# PhychipDevelopmentBoard.net
KiCad netlist of a schematic drawn in EAGLE
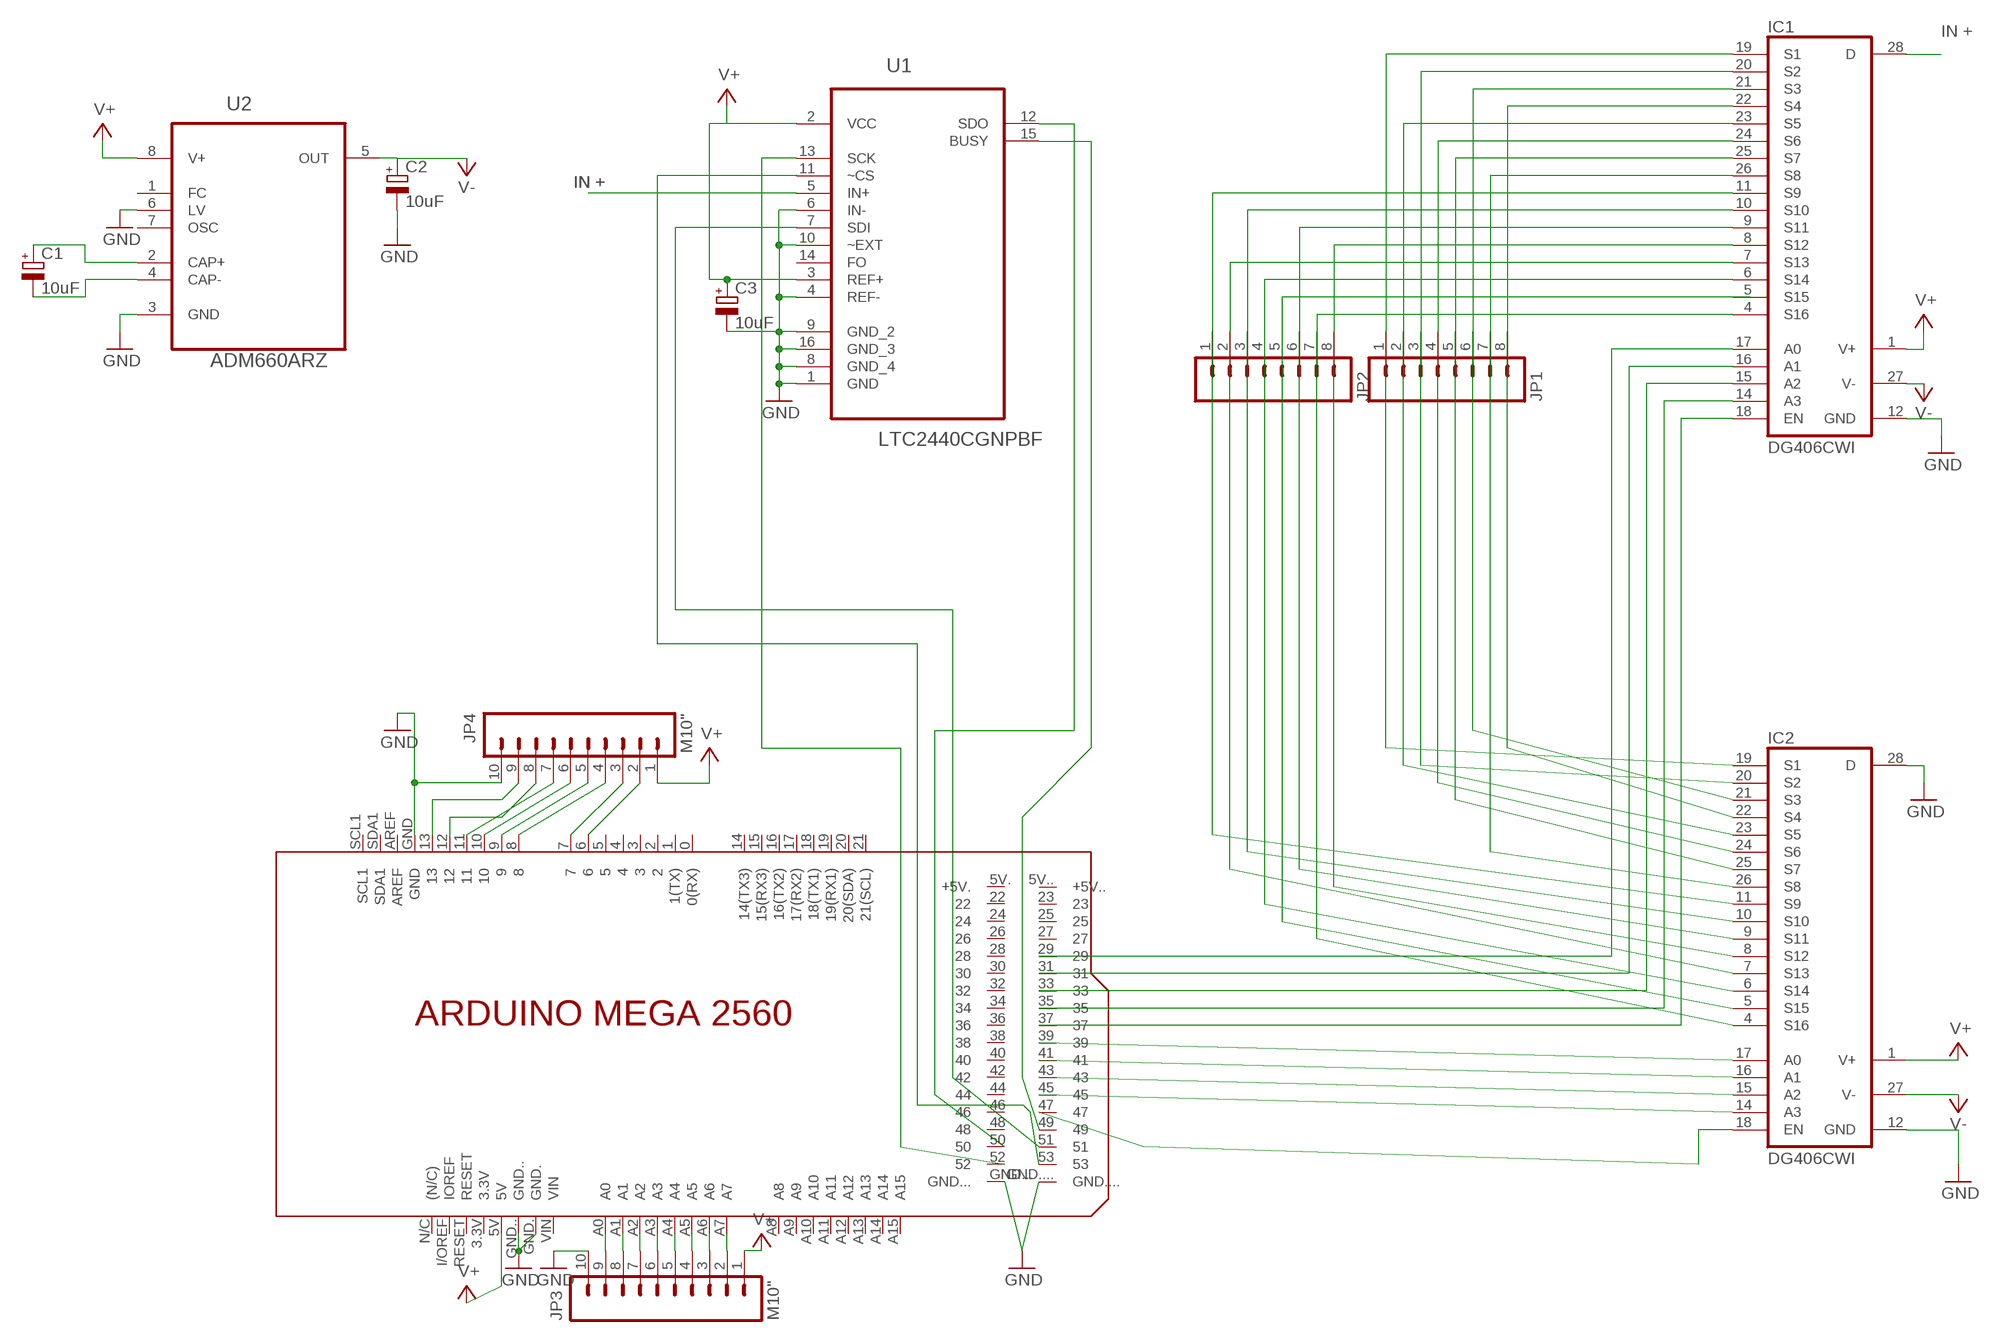
[diagram p0: schematic, sheet 1]

(export (version "E")
  (design (tool "Eeschema 10.0.6"))
  (components
    (comp (ref "C1")
      (value "10uF")
      (footprint "eagle-import:153CLV-0505")
      (libsource (lib "eagle-import") (part "CPOL-EU153CLV-0505"))
    )
    (comp (ref "C2")
      (value "10uF")
      (footprint "eagle-import:153CLV-0505")
      (libsource (lib "eagle-import") (part "CPOL-EU153CLV-0505"))
    )
    (comp (ref "C3")
      (value "10uF")
      (footprint "eagle-import:153CLV-0505")
      (libsource (lib "eagle-import") (part "CPOL-EU153CLV-0505"))
    )
    (comp (ref "IC1")
      (value "DG406CWI")
      (footprint "eagle-import:SO28L")
      (fields (field (name "MF") "MAXIM"))
      (libsource (lib "eagle-import") (part "DG406CWI"))
    )
    (comp (ref "IC2")
      (value "DG406CWI")
      (footprint "eagle-import:SO28L")
      (fields (field (name "MF") "MAXIM"))
      (libsource (lib "eagle-import") (part "DG406CWI"))
    )
    (comp (ref "JP1")
      (value "M08")
      (footprint "eagle-import:1X08")
      (libsource (lib "eagle-import") (part "M08"))
    )
    (comp (ref "JP2")
      (value "M08")
      (footprint "eagle-import:1X08")
      (libsource (lib "eagle-import") (part "M08"))
    )
    (comp (ref "JP3")
      (value "M10\"")
      (footprint "eagle-import:1X10")
      (libsource (lib "eagle-import") (part "M10{dblquote}"))
    )
    (comp (ref "JP4")
      (value "M10\"")
      (footprint "eagle-import:1X10")
      (libsource (lib "eagle-import") (part "M10{dblquote}"))
    )
    (comp (ref "PCB1")
      (value "ARDUINO_MEGA2560")
      (footprint "eagle-import:ARDUINO_MEGA2560")
      (libsource (lib "eagle-import") (part "ARDUINO_MEGA2560"))
    )
    (comp (ref "U1")
      (value "LTC2440CGNPBF")
      (footprint "eagle-import:SOP63P600X175-16N")
      (fields (field (name "MPN") "LTC2440CGN#PBF"))
      (libsource (lib "eagle-import") (part "LTC2440CGNPBF"))
    )
    (comp (ref "U2")
      (value "ADM660ARZ")
      (footprint "eagle-import:SOIC127P600X175-8N")
      (libsource (lib "eagle-import") (part "ADM660ARZ"))
    )
  )
  (nets
    (net (code "1") (name "/IN+") (class "Default")
      (node (ref "IC1") (pin "28") (pinfunction "D_28") (pintype "passive"))
      (node (ref "U1") (pin "5") (pinfunction "IN+_5") (pintype "input"))
    )
    (net (code "2") (name "GND") (class "Default")
      (node (ref "C2") (pin "-") (pinfunction "-_-") (pintype "passive"))
      (node (ref "C3") (pin "-") (pinfunction "-_-") (pintype "passive"))
      (node (ref "IC1") (pin "12") (pinfunction "GND_12") (pintype "power_in"))
      (node (ref "IC2") (pin "12") (pinfunction "GND_12") (pintype "power_in"))
      (node (ref "IC2") (pin "28") (pinfunction "D_28") (pintype "passive"))
      (node (ref "JP3") (pin "10") (pinfunction "10_10") (pintype "passive"))
      (node (ref "JP4") (pin "10") (pinfunction "10_10") (pintype "passive"))
      (node (ref "PCB1") (pin "GND") (pinfunction "GND_GND") (pintype "bidirectional"))
      (node (ref "PCB1") (pin "GND.") (pinfunction "GND._GND.") (pintype "bidirectional"))
      (node (ref "PCB1") (pin "GND..") (pinfunction "GND.._GND..") (pintype "bidirectional"))
      (node (ref "PCB1") (pin "GND...") (pinfunction "GND..._GND...") (pintype "bidirectional"))
      (node (ref "PCB1") (pin "GND....") (pinfunction "GND...._GND....") (pintype "bidirectional"))
      (node (ref "U1") (pin "1") (pinfunction "GND_1") (pintype "passive"))
      (node (ref "U1") (pin "10") (pinfunction "~{EXT}_10") (pintype "input"))
      (node (ref "U1") (pin "16") (pinfunction "GND_3_16") (pintype "passive"))
      (node (ref "U1") (pin "4") (pinfunction "REF-_4") (pintype "input"))
      (node (ref "U1") (pin "6") (pinfunction "IN-_6") (pintype "input"))
      (node (ref "U1") (pin "8") (pinfunction "GND_4_8") (pintype "passive"))
      (node (ref "U1") (pin "9") (pinfunction "GND_2_9") (pintype "passive"))
      (node (ref "U2") (pin "3") (pinfunction "GND_3") (pintype "passive"))
      (node (ref "U2") (pin "6") (pinfunction "LV_6") (pintype "input"))
    )
    (net (code "3") (name "Net-(IC1-A0)") (class "Default")
      (node (ref "IC1") (pin "17") (pinfunction "A0_17") (pintype "input"))
      (node (ref "PCB1") (pin "29") (pinfunction "29_29") (pintype "bidirectional"))
    )
    (net (code "4") (name "Net-(IC1-A1)") (class "Default")
      (node (ref "IC1") (pin "16") (pinfunction "A1_16") (pintype "input"))
      (node (ref "PCB1") (pin "31") (pinfunction "31_31") (pintype "bidirectional"))
    )
    (net (code "5") (name "Net-(IC1-A2)") (class "Default")
      (node (ref "IC1") (pin "15") (pinfunction "A2_15") (pintype "input"))
      (node (ref "PCB1") (pin "33") (pinfunction "33_33") (pintype "bidirectional"))
    )
    (net (code "6") (name "Net-(IC1-A3)") (class "Default")
      (node (ref "IC1") (pin "14") (pinfunction "A3_14") (pintype "input"))
      (node (ref "PCB1") (pin "35") (pinfunction "35_35") (pintype "bidirectional"))
    )
    (net (code "7") (name "Net-(IC1-EN)") (class "Default")
      (node (ref "IC1") (pin "18") (pinfunction "EN_18") (pintype "input"))
      (node (ref "PCB1") (pin "37") (pinfunction "37_37") (pintype "bidirectional"))
    )
    (net (code "8") (name "Net-(IC1-S1)") (class "Default")
      (node (ref "IC1") (pin "19") (pinfunction "S1_19") (pintype "passive"))
      (node (ref "IC2") (pin "19") (pinfunction "S1_19") (pintype "passive"))
      (node (ref "JP1") (pin "1") (pinfunction "1_1") (pintype "passive"))
    )
    (net (code "9") (name "Net-(IC1-S2)") (class "Default")
      (node (ref "IC1") (pin "20") (pinfunction "S2_20") (pintype "passive"))
      (node (ref "IC2") (pin "20") (pinfunction "S2_20") (pintype "passive"))
      (node (ref "JP1") (pin "3") (pinfunction "3_3") (pintype "passive"))
    )
    (net (code "10") (name "Net-(IC1-S3)") (class "Default")
      (node (ref "IC1") (pin "21") (pinfunction "S3_21") (pintype "passive"))
      (node (ref "IC2") (pin "21") (pinfunction "S3_21") (pintype "passive"))
      (node (ref "JP1") (pin "6") (pinfunction "6_6") (pintype "passive"))
    )
    (net (code "11") (name "Net-(IC1-S4)") (class "Default")
      (node (ref "IC1") (pin "22") (pinfunction "S4_22") (pintype "passive"))
      (node (ref "IC2") (pin "22") (pinfunction "S4_22") (pintype "passive"))
      (node (ref "JP1") (pin "8") (pinfunction "8_8") (pintype "passive"))
    )
    (net (code "12") (name "Net-(IC1-S5)") (class "Default")
      (node (ref "IC1") (pin "23") (pinfunction "S5_23") (pintype "passive"))
      (node (ref "IC2") (pin "23") (pinfunction "S5_23") (pintype "passive"))
      (node (ref "JP1") (pin "2") (pinfunction "2_2") (pintype "passive"))
    )
    (net (code "13") (name "Net-(IC1-S6)") (class "Default")
      (node (ref "IC1") (pin "24") (pinfunction "S6_24") (pintype "passive"))
      (node (ref "IC2") (pin "24") (pinfunction "S6_24") (pintype "passive"))
      (node (ref "JP1") (pin "4") (pinfunction "4_4") (pintype "passive"))
    )
    (net (code "14") (name "Net-(IC1-S7)") (class "Default")
      (node (ref "IC1") (pin "25") (pinfunction "S7_25") (pintype "passive"))
      (node (ref "IC2") (pin "25") (pinfunction "S7_25") (pintype "passive"))
      (node (ref "JP1") (pin "5") (pinfunction "5_5") (pintype "passive"))
    )
    (net (code "15") (name "Net-(IC1-S8)") (class "Default")
      (node (ref "IC1") (pin "26") (pinfunction "S8_26") (pintype "passive"))
      (node (ref "IC2") (pin "26") (pinfunction "S8_26") (pintype "passive"))
      (node (ref "JP1") (pin "7") (pinfunction "7_7") (pintype "passive"))
    )
    (net (code "16") (name "Net-(IC1-S9)") (class "Default")
      (node (ref "IC1") (pin "11") (pinfunction "S9_11") (pintype "passive"))
      (node (ref "IC2") (pin "11") (pinfunction "S9_11") (pintype "passive"))
      (node (ref "JP2") (pin "1") (pinfunction "1_1") (pintype "passive"))
    )
    (net (code "17") (name "Net-(IC1-S10)") (class "Default")
      (node (ref "IC1") (pin "10") (pinfunction "S10_10") (pintype "passive"))
      (node (ref "IC2") (pin "10") (pinfunction "S10_10") (pintype "passive"))
      (node (ref "JP2") (pin "3") (pinfunction "3_3") (pintype "passive"))
    )
    (net (code "18") (name "Net-(IC1-S11)") (class "Default")
      (node (ref "IC1") (pin "9") (pinfunction "S11_9") (pintype "passive"))
      (node (ref "IC2") (pin "9") (pinfunction "S11_9") (pintype "passive"))
      (node (ref "JP2") (pin "6") (pinfunction "6_6") (pintype "passive"))
    )
    (net (code "19") (name "Net-(IC1-S12)") (class "Default")
      (node (ref "IC1") (pin "8") (pinfunction "S12_8") (pintype "passive"))
      (node (ref "IC2") (pin "8") (pinfunction "S12_8") (pintype "passive"))
      (node (ref "JP2") (pin "8") (pinfunction "8_8") (pintype "passive"))
    )
    (net (code "20") (name "Net-(IC1-S13)") (class "Default")
      (node (ref "IC1") (pin "7") (pinfunction "S13_7") (pintype "passive"))
      (node (ref "IC2") (pin "7") (pinfunction "S13_7") (pintype "passive"))
      (node (ref "JP2") (pin "2") (pinfunction "2_2") (pintype "passive"))
    )
    (net (code "21") (name "Net-(IC1-S14)") (class "Default")
      (node (ref "IC1") (pin "6") (pinfunction "S14_6") (pintype "passive"))
      (node (ref "IC2") (pin "6") (pinfunction "S14_6") (pintype "passive"))
      (node (ref "JP2") (pin "4") (pinfunction "4_4") (pintype "passive"))
    )
    (net (code "22") (name "Net-(IC1-S16)") (class "Default")
      (node (ref "IC1") (pin "4") (pinfunction "S16_4") (pintype "passive"))
      (node (ref "IC2") (pin "4") (pinfunction "S16_4") (pintype "passive"))
      (node (ref "JP2") (pin "7") (pinfunction "7_7") (pintype "passive"))
    )
    (net (code "23") (name "Net-(IC2-A0)") (class "Default")
      (node (ref "IC2") (pin "17") (pinfunction "A0_17") (pintype "input"))
      (node (ref "PCB1") (pin "39") (pinfunction "39_39") (pintype "bidirectional"))
    )
    (net (code "24") (name "Net-(IC2-A1)") (class "Default")
      (node (ref "IC2") (pin "16") (pinfunction "A1_16") (pintype "input"))
      (node (ref "PCB1") (pin "41") (pinfunction "41_41") (pintype "bidirectional"))
    )
    (net (code "25") (name "Net-(IC2-A2)") (class "Default")
      (node (ref "IC2") (pin "15") (pinfunction "A2_15") (pintype "input"))
      (node (ref "PCB1") (pin "43") (pinfunction "43_43") (pintype "bidirectional"))
    )
    (net (code "26") (name "Net-(IC2-A3)") (class "Default")
      (node (ref "IC2") (pin "14") (pinfunction "A3_14") (pintype "input"))
      (node (ref "PCB1") (pin "45") (pinfunction "45_45") (pintype "bidirectional"))
    )
    (net (code "27") (name "Net-(IC2-EN)") (class "Default")
      (node (ref "IC2") (pin "18") (pinfunction "EN_18") (pintype "input"))
      (node (ref "PCB1") (pin "47") (pinfunction "47_47") (pintype "bidirectional"))
    )
    (net (code "28") (name "Net-(IC2-S15)") (class "Default")
      (node (ref "IC2") (pin "5") (pinfunction "S15_5") (pintype "passive"))
      (node (ref "JP2") (pin "5") (pinfunction "5_5") (pintype "passive"))
    )
    (net (code "29") (name "Net-(JP3-Pad2)") (class "Default")
      (node (ref "JP3") (pin "2") (pinfunction "2_2") (pintype "passive"))
      (node (ref "PCB1") (pin "A7") (pinfunction "A7_A7") (pintype "bidirectional"))
    )
    (net (code "30") (name "Net-(JP3-Pad3)") (class "Default")
      (node (ref "JP3") (pin "3") (pinfunction "3_3") (pintype "passive"))
      (node (ref "PCB1") (pin "A6") (pinfunction "A6_A6") (pintype "bidirectional"))
    )
    (net (code "31") (name "Net-(JP3-Pad4)") (class "Default")
      (node (ref "JP3") (pin "4") (pinfunction "4_4") (pintype "passive"))
      (node (ref "PCB1") (pin "A5") (pinfunction "A5_A5") (pintype "bidirectional"))
    )
    (net (code "32") (name "Net-(JP3-Pad5)") (class "Default")
      (node (ref "JP3") (pin "5") (pinfunction "5_5") (pintype "passive"))
      (node (ref "PCB1") (pin "A4") (pinfunction "A4_A4") (pintype "bidirectional"))
    )
    (net (code "33") (name "Net-(JP3-Pad6)") (class "Default")
      (node (ref "JP3") (pin "6") (pinfunction "6_6") (pintype "passive"))
      (node (ref "PCB1") (pin "A3") (pinfunction "A3_A3") (pintype "bidirectional"))
    )
    (net (code "34") (name "Net-(JP3-Pad7)") (class "Default")
      (node (ref "JP3") (pin "7") (pinfunction "7_7") (pintype "passive"))
      (node (ref "PCB1") (pin "A2") (pinfunction "A2_A2") (pintype "bidirectional"))
    )
    (net (code "35") (name "Net-(JP3-Pad8)") (class "Default")
      (node (ref "JP3") (pin "8") (pinfunction "8_8") (pintype "passive"))
      (node (ref "PCB1") (pin "A1") (pinfunction "A1_A1") (pintype "bidirectional"))
    )
    (net (code "36") (name "Net-(JP3-Pad9)") (class "Default")
      (node (ref "JP3") (pin "9") (pinfunction "9_9") (pintype "passive"))
      (node (ref "PCB1") (pin "A0") (pinfunction "A0_A0") (pintype "bidirectional"))
    )
    (net (code "37") (name "Net-(JP4-Pad2)") (class "Default")
      (node (ref "JP4") (pin "2") (pinfunction "2_2") (pintype "passive"))
      (node (ref "PCB1") (pin "6") (pinfunction "6_6") (pintype "bidirectional"))
    )
    (net (code "38") (name "Net-(JP4-Pad3)") (class "Default")
      (node (ref "JP4") (pin "3") (pinfunction "3_3") (pintype "passive"))
      (node (ref "PCB1") (pin "7") (pinfunction "7_7") (pintype "bidirectional"))
    )
    (net (code "39") (name "Net-(JP4-Pad4)") (class "Default")
      (node (ref "JP4") (pin "4") (pinfunction "4_4") (pintype "passive"))
      (node (ref "PCB1") (pin "8") (pinfunction "8_8") (pintype "bidirectional"))
    )
    (net (code "40") (name "Net-(JP4-Pad5)") (class "Default")
      (node (ref "JP4") (pin "5") (pinfunction "5_5") (pintype "passive"))
      (node (ref "PCB1") (pin "9") (pinfunction "9_9") (pintype "bidirectional"))
    )
    (net (code "41") (name "Net-(JP4-Pad6)") (class "Default")
      (node (ref "JP4") (pin "6") (pinfunction "6_6") (pintype "passive"))
      (node (ref "PCB1") (pin "10") (pinfunction "10_10") (pintype "bidirectional"))
    )
    (net (code "42") (name "Net-(JP4-Pad7)") (class "Default")
      (node (ref "JP4") (pin "7") (pinfunction "7_7") (pintype "passive"))
      (node (ref "PCB1") (pin "11") (pinfunction "11_11") (pintype "bidirectional"))
    )
    (net (code "43") (name "Net-(JP4-Pad8)") (class "Default")
      (node (ref "JP4") (pin "8") (pinfunction "8_8") (pintype "passive"))
      (node (ref "PCB1") (pin "12") (pinfunction "12_12") (pintype "bidirectional"))
    )
    (net (code "44") (name "Net-(JP4-Pad9)") (class "Default")
      (node (ref "JP4") (pin "9") (pinfunction "9_9") (pintype "passive"))
      (node (ref "PCB1") (pin "13") (pinfunction "13_13") (pintype "bidirectional"))
    )
    (net (code "45") (name "Net-(U1-BUSY)") (class "Default")
      (node (ref "PCB1") (pin "49") (pinfunction "49_49") (pintype "bidirectional"))
      (node (ref "U1") (pin "15") (pinfunction "BUSY_15") (pintype "output"))
    )
    (net (code "46") (name "Net-(U1-SCK)") (class "Default")
      (node (ref "PCB1") (pin "52") (pinfunction "52_52") (pintype "bidirectional"))
      (node (ref "U1") (pin "13") (pinfunction "SCK_13") (pintype "input"))
    )
    (net (code "47") (name "Net-(U1-SDI)") (class "Default")
      (node (ref "PCB1") (pin "51") (pinfunction "51_51") (pintype "bidirectional"))
      (node (ref "U1") (pin "7") (pinfunction "SDI_7") (pintype "input"))
    )
    (net (code "48") (name "Net-(U1-SDO)") (class "Default")
      (node (ref "PCB1") (pin "50") (pinfunction "50_50") (pintype "bidirectional"))
      (node (ref "U1") (pin "12") (pinfunction "SDO_12") (pintype "output"))
    )
    (net (code "49") (name "Net-(U1-~{CS})") (class "Default")
      (node (ref "PCB1") (pin "53") (pinfunction "53_53") (pintype "bidirectional"))
      (node (ref "U1") (pin "11") (pinfunction "~{CS}_11") (pintype "input"))
    )
    (net (code "50") (name "Net-(U2-CAP+)") (class "Default")
      (node (ref "C1") (pin "+") (pinfunction "+_+") (pintype "passive"))
      (node (ref "U2") (pin "2") (pinfunction "CAP+_2") (pintype "input"))
    )
    (net (code "51") (name "Net-(U2-CAP-)") (class "Default")
      (node (ref "C1") (pin "-") (pinfunction "-_-") (pintype "passive"))
      (node (ref "U2") (pin "4") (pinfunction "CAP-_4") (pintype "input"))
    )
    (net (code "52") (name "V+") (class "Default")
      (node (ref "C3") (pin "+") (pinfunction "+_+") (pintype "passive"))
      (node (ref "IC1") (pin "1") (pinfunction "V+_1") (pintype "power_in"))
      (node (ref "IC2") (pin "1") (pinfunction "V+_1") (pintype "power_in"))
      (node (ref "JP3") (pin "1") (pinfunction "1_1") (pintype "passive"))
      (node (ref "JP4") (pin "1") (pinfunction "1_1") (pintype "passive"))
      (node (ref "PCB1") (pin "5V") (pinfunction "5V_5V") (pintype "bidirectional"))
      (node (ref "U1") (pin "2") (pinfunction "VCC_2") (pintype "power_in"))
      (node (ref "U1") (pin "3") (pinfunction "REF+_3") (pintype "input"))
      (node (ref "U2") (pin "8") (pinfunction "V+_8") (pintype "power_in"))
    )
    (net (code "53") (name "V-") (class "Default")
      (node (ref "C2") (pin "+") (pinfunction "+_+") (pintype "passive"))
      (node (ref "IC1") (pin "27") (pinfunction "V-_27") (pintype "power_in"))
      (node (ref "IC2") (pin "27") (pinfunction "V-_27") (pintype "power_in"))
      (node (ref "U2") (pin "5") (pinfunction "OUT_5") (pintype "output"))
    )
    (net (code "54") (name "unconnected-(IC1-S15-Pad5)") (class "Default")
      (node (ref "IC1") (pin "5") (pinfunction "S15_5") (pintype "passive"))
    )
    (net (code "55") (name "unconnected-(PCB1-(N{slash}C)-PadN{slash}C)") (class "Default")
      (node (ref "PCB1") (pin "N/C") (pinfunction "(N/C)_N/C") (pintype "bidirectional"))
    )
    (net (code "56") (name "unconnected-(PCB1-+5V.-Pad5V.)") (class "Default")
      (node (ref "PCB1") (pin "5V.") (pinfunction "+5V._5V.") (pintype "bidirectional"))
    )
    (net (code "57") (name "unconnected-(PCB1-+5V..-Pad5V..)") (class "Default")
      (node (ref "PCB1") (pin "5V..") (pinfunction "+5V.._5V..") (pintype "bidirectional"))
    )
    (net (code "58") (name "unconnected-(PCB1-0(RX)-Pad0)") (class "Default")
      (node (ref "PCB1") (pin "0") (pinfunction "0(RX)_0") (pintype "bidirectional"))
    )
    (net (code "59") (name "unconnected-(PCB1-1(TX)-Pad1)") (class "Default")
      (node (ref "PCB1") (pin "1") (pinfunction "1(TX)_1") (pintype "bidirectional"))
    )
    (net (code "60") (name "unconnected-(PCB1-14(TX3)-Pad14)") (class "Default")
      (node (ref "PCB1") (pin "14") (pinfunction "14(TX3)_14") (pintype "bidirectional"))
    )
    (net (code "61") (name "unconnected-(PCB1-15(RX3)-Pad15)") (class "Default")
      (node (ref "PCB1") (pin "15") (pinfunction "15(RX3)_15") (pintype "bidirectional"))
    )
    (net (code "62") (name "unconnected-(PCB1-16(TX2)-Pad16)") (class "Default")
      (node (ref "PCB1") (pin "16") (pinfunction "16(TX2)_16") (pintype "bidirectional"))
    )
    (net (code "63") (name "unconnected-(PCB1-17(RX2)-Pad17)") (class "Default")
      (node (ref "PCB1") (pin "17") (pinfunction "17(RX2)_17") (pintype "bidirectional"))
    )
    (net (code "64") (name "unconnected-(PCB1-18(TX1)-Pad18)") (class "Default")
      (node (ref "PCB1") (pin "18") (pinfunction "18(TX1)_18") (pintype "bidirectional"))
    )
    (net (code "65") (name "unconnected-(PCB1-19(RX1)-Pad19)") (class "Default")
      (node (ref "PCB1") (pin "19") (pinfunction "19(RX1)_19") (pintype "bidirectional"))
    )
    (net (code "66") (name "unconnected-(PCB1-20(SDA)-Pad20)") (class "Default")
      (node (ref "PCB1") (pin "20") (pinfunction "20(SDA)_20") (pintype "bidirectional"))
    )
    (net (code "67") (name "unconnected-(PCB1-21(SCL)-Pad21)") (class "Default")
      (node (ref "PCB1") (pin "21") (pinfunction "21(SCL)_21") (pintype "bidirectional"))
    )
    (net (code "68") (name "unconnected-(PCB1-IOREF-PadI{slash}OREF)") (class "Default")
      (node (ref "PCB1") (pin "I/OREF") (pinfunction "IOREF_I/OREF") (pintype "bidirectional"))
    )
    (net (code "69") (name "unconnected-(PCB1-Pad2)") (class "Default")
      (node (ref "PCB1") (pin "2") (pinfunction "2_2") (pintype "bidirectional"))
    )
    (net (code "70") (name "unconnected-(PCB1-Pad3)") (class "Default")
      (node (ref "PCB1") (pin "3") (pinfunction "3_3") (pintype "bidirectional"))
    )
    (net (code "71") (name "unconnected-(PCB1-Pad3.3V)") (class "Default")
      (node (ref "PCB1") (pin "3.3V") (pinfunction "3.3V_3.3V") (pintype "bidirectional"))
    )
    (net (code "72") (name "unconnected-(PCB1-Pad4)") (class "Default")
      (node (ref "PCB1") (pin "4") (pinfunction "4_4") (pintype "bidirectional"))
    )
    (net (code "73") (name "unconnected-(PCB1-Pad5)") (class "Default")
      (node (ref "PCB1") (pin "5") (pinfunction "5_5") (pintype "bidirectional"))
    )
    (net (code "74") (name "unconnected-(PCB1-Pad22)") (class "Default")
      (node (ref "PCB1") (pin "22") (pinfunction "22_22") (pintype "bidirectional"))
    )
    (net (code "75") (name "unconnected-(PCB1-Pad23)") (class "Default")
      (node (ref "PCB1") (pin "23") (pinfunction "23_23") (pintype "bidirectional"))
    )
    (net (code "76") (name "unconnected-(PCB1-Pad24)") (class "Default")
      (node (ref "PCB1") (pin "24") (pinfunction "24_24") (pintype "bidirectional"))
    )
    (net (code "77") (name "unconnected-(PCB1-Pad25)") (class "Default")
      (node (ref "PCB1") (pin "25") (pinfunction "25_25") (pintype "bidirectional"))
    )
    (net (code "78") (name "unconnected-(PCB1-Pad26)") (class "Default")
      (node (ref "PCB1") (pin "26") (pinfunction "26_26") (pintype "bidirectional"))
    )
    (net (code "79") (name "unconnected-(PCB1-Pad27)") (class "Default")
      (node (ref "PCB1") (pin "27") (pinfunction "27_27") (pintype "bidirectional"))
    )
    (net (code "80") (name "unconnected-(PCB1-Pad28)") (class "Default")
      (node (ref "PCB1") (pin "28") (pinfunction "28_28") (pintype "bidirectional"))
    )
    (net (code "81") (name "unconnected-(PCB1-Pad30)") (class "Default")
      (node (ref "PCB1") (pin "30") (pinfunction "30_30") (pintype "bidirectional"))
    )
    (net (code "82") (name "unconnected-(PCB1-Pad32)") (class "Default")
      (node (ref "PCB1") (pin "32") (pinfunction "32_32") (pintype "bidirectional"))
    )
    (net (code "83") (name "unconnected-(PCB1-Pad34)") (class "Default")
      (node (ref "PCB1") (pin "34") (pinfunction "34_34") (pintype "bidirectional"))
    )
    (net (code "84") (name "unconnected-(PCB1-Pad36)") (class "Default")
      (node (ref "PCB1") (pin "36") (pinfunction "36_36") (pintype "bidirectional"))
    )
    (net (code "85") (name "unconnected-(PCB1-Pad38)") (class "Default")
      (node (ref "PCB1") (pin "38") (pinfunction "38_38") (pintype "bidirectional"))
    )
    (net (code "86") (name "unconnected-(PCB1-Pad40)") (class "Default")
      (node (ref "PCB1") (pin "40") (pinfunction "40_40") (pintype "bidirectional"))
    )
    (net (code "87") (name "unconnected-(PCB1-Pad42)") (class "Default")
      (node (ref "PCB1") (pin "42") (pinfunction "42_42") (pintype "bidirectional"))
    )
    (net (code "88") (name "unconnected-(PCB1-Pad44)") (class "Default")
      (node (ref "PCB1") (pin "44") (pinfunction "44_44") (pintype "bidirectional"))
    )
    (net (code "89") (name "unconnected-(PCB1-Pad46)") (class "Default")
      (node (ref "PCB1") (pin "46") (pinfunction "46_46") (pintype "bidirectional"))
    )
    (net (code "90") (name "unconnected-(PCB1-Pad48)") (class "Default")
      (node (ref "PCB1") (pin "48") (pinfunction "48_48") (pintype "bidirectional"))
    )
    (net (code "91") (name "unconnected-(PCB1-PadA8)") (class "Default")
      (node (ref "PCB1") (pin "A8") (pinfunction "A8_A8") (pintype "bidirectional"))
    )
    (net (code "92") (name "unconnected-(PCB1-PadA9)") (class "Default")
      (node (ref "PCB1") (pin "A9") (pinfunction "A9_A9") (pintype "bidirectional"))
    )
    (net (code "93") (name "unconnected-(PCB1-PadA10)") (class "Default")
      (node (ref "PCB1") (pin "A10") (pinfunction "A10_A10") (pintype "bidirectional"))
    )
    (net (code "94") (name "unconnected-(PCB1-PadA11)") (class "Default")
      (node (ref "PCB1") (pin "A11") (pinfunction "A11_A11") (pintype "bidirectional"))
    )
    (net (code "95") (name "unconnected-(PCB1-PadA12)") (class "Default")
      (node (ref "PCB1") (pin "A12") (pinfunction "A12_A12") (pintype "bidirectional"))
    )
    (net (code "96") (name "unconnected-(PCB1-PadA13)") (class "Default")
      (node (ref "PCB1") (pin "A13") (pinfunction "A13_A13") (pintype "bidirectional"))
    )
    (net (code "97") (name "unconnected-(PCB1-PadA14)") (class "Default")
      (node (ref "PCB1") (pin "A14") (pinfunction "A14_A14") (pintype "bidirectional"))
    )
    (net (code "98") (name "unconnected-(PCB1-PadA15)") (class "Default")
      (node (ref "PCB1") (pin "A15") (pinfunction "A15_A15") (pintype "bidirectional"))
    )
    (net (code "99") (name "unconnected-(PCB1-PadAREF)") (class "Default")
      (node (ref "PCB1") (pin "AREF") (pinfunction "AREF_AREF") (pintype "bidirectional"))
    )
    (net (code "100") (name "unconnected-(PCB1-PadRESET)") (class "Default")
      (node (ref "PCB1") (pin "RESET") (pinfunction "RESET_RESET") (pintype "bidirectional"))
    )
    (net (code "101") (name "unconnected-(PCB1-PadSCL1)") (class "Default")
      (node (ref "PCB1") (pin "SCL1") (pinfunction "SCL1_SCL1") (pintype "bidirectional"))
    )
    (net (code "102") (name "unconnected-(PCB1-PadSDA1)") (class "Default")
      (node (ref "PCB1") (pin "SDA1") (pinfunction "SDA1_SDA1") (pintype "bidirectional"))
    )
    (net (code "103") (name "unconnected-(PCB1-PadVIN)") (class "Default")
      (node (ref "PCB1") (pin "VIN") (pinfunction "VIN_VIN") (pintype "bidirectional"))
    )
    (net (code "104") (name "unconnected-(U1-FO-Pad14)") (class "Default")
      (node (ref "U1") (pin "14") (pinfunction "FO_14") (pintype "input"))
    )
    (net (code "105") (name "unconnected-(U2-FC-Pad1)") (class "Default")
      (node (ref "U2") (pin "1") (pinfunction "FC_1") (pintype "input"))
    )
    (net (code "106") (name "unconnected-(U2-OSC-Pad7)") (class "Default")
      (node (ref "U2") (pin "7") (pinfunction "OSC_7") (pintype "input"))
    )
  )
)
